# Z80Board.net
KiCad netlist of a schematic drawn in EAGLE
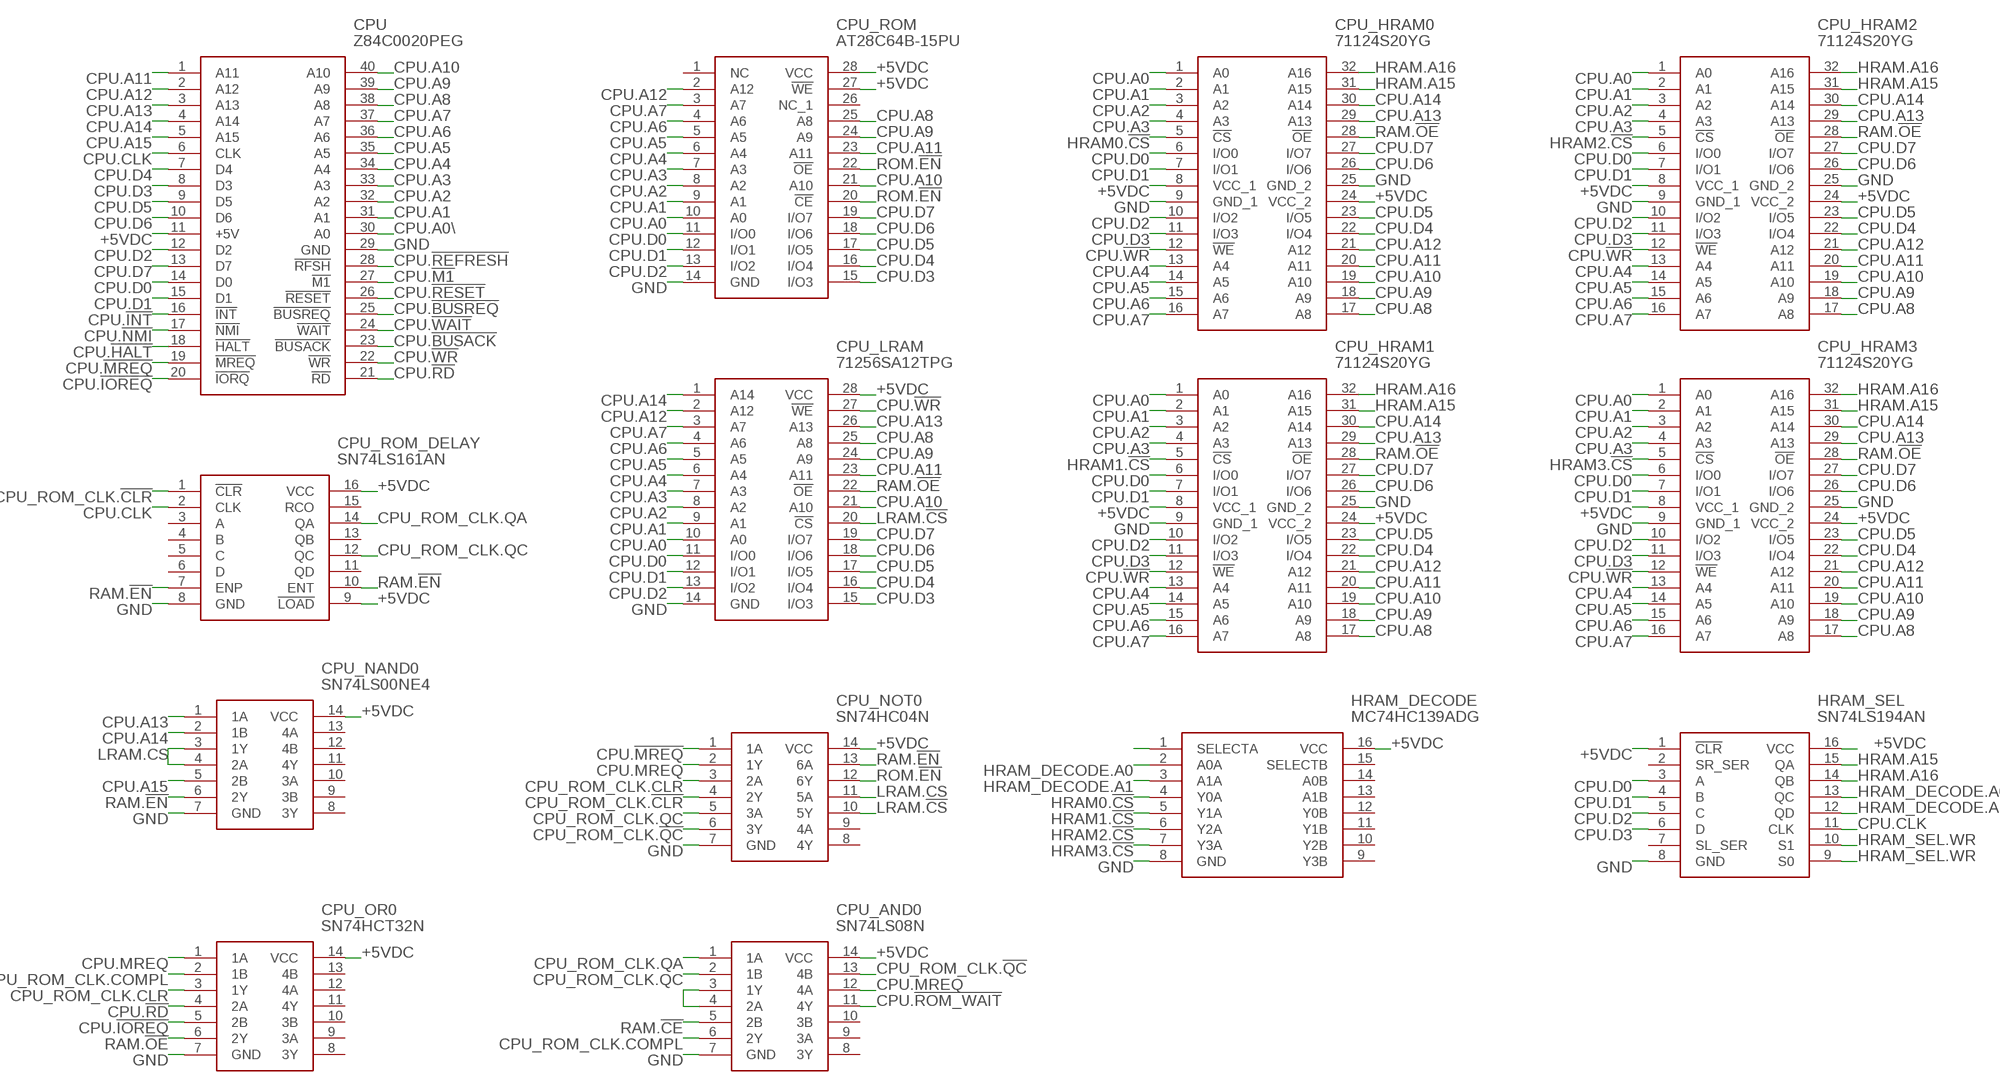
[diagram p0: schematic, sheet 1]

(export (version "E")
  (design (tool "Eeschema 10.0.6"))
  (components
    (comp (ref "CPU")
      (value "Z84C0020PEG")
      (footprint "eagle-import:DIP1612W53P254L5232H406Q40N")
      (libsource (lib "eagle-import") (part "Z84C0020PEG"))
    )
    (comp (ref "CPU_AND0")
      (value "SN74LS08N")
      (footprint "eagle-import:DIP794W53P254L1930H508Q14N")
      (fields (field (name "MOUSER_PART_NUMBER") "595-SN74LS08N") (field (name "RS_PART_NUMBER") "0307519P"))
      (libsource (lib "eagle-import") (part "SN74LS08N"))
    )
    (comp (ref "CPU_HRAM0")
      (value "71124S20YG")
      (footprint "eagle-import:71124S20YG")
      (fields (field (name "MOUSER_PART_NUMBER") "972-71124S20YG"))
      (libsource (lib "eagle-import") (part "71124S20YG"))
    )
    (comp (ref "CPU_HRAM1")
      (value "71124S20YG")
      (footprint "eagle-import:71124S20YG")
      (fields (field (name "MOUSER_PART_NUMBER") "972-71124S20YG"))
      (libsource (lib "eagle-import") (part "71124S20YG"))
    )
    (comp (ref "CPU_HRAM2")
      (value "71124S20YG")
      (footprint "eagle-import:71124S20YG")
      (fields (field (name "MOUSER_PART_NUMBER") "972-71124S20YG"))
      (libsource (lib "eagle-import") (part "71124S20YG"))
    )
    (comp (ref "CPU_HRAM3")
      (value "71124S20YG")
      (footprint "eagle-import:71124S20YG")
      (fields (field (name "MOUSER_PART_NUMBER") "972-71124S20YG"))
      (libsource (lib "eagle-import") (part "71124S20YG"))
    )
    (comp (ref "CPU_LRAM")
      (value "71256SA12TPG")
      (footprint "eagle-import:DIP851W46P254L3556H330Q28N")
      (libsource (lib "eagle-import") (part "71256SA12TPG"))
    )
    (comp (ref "CPU_NAND0")
      (value "SN74LS00NE4")
      (footprint "eagle-import:DIP794W53P254L1930H508Q14N")
      (fields (field (name "MOUSER_PART_NUMBER") "595-SN74LS00NE4"))
      (libsource (lib "eagle-import") (part "SN74LS00NE4"))
    )
    (comp (ref "CPU_NOT0")
      (value "SN74HC04N")
      (footprint "eagle-import:DIP794W53P254L1930H508Q14N")
      (fields (field (name "MOUSER_PART_NUMBER") "595-SN74HC04N") (field (name "RS_PART_NUMBER") "2175550P"))
      (libsource (lib "eagle-import") (part "SN74HC04N"))
    )
    (comp (ref "CPU_OR0")
      (value "SN74HCT32N")
      (footprint "eagle-import:DIP794W53P254L1930H508Q14N")
      (fields (field (name "MOUSER_PART_NUMBER") "595-SN74HCT32N") (field (name "RS_PART_NUMBER") "2175768P"))
      (libsource (lib "eagle-import") (part "SN74HCT32N"))
    )
    (comp (ref "CPU_ROM")
      (value "AT28C64B-15PU")
      (footprint "eagle-import:DIP1556W56P254L3702H483Q28N")
      (fields
        (field (name "MOUSER_PART_NUMBER") "556-AT28C64B15PU")
        (field (name "RS_PART_NUMBER") "2509609978")
      )
      (libsource (lib "eagle-import") (part "AT28C64B-15PU"))
    )
    (comp (ref "CPU_ROM_DELAY")
      (value "SN74LS161AN")
      (footprint "eagle-import:DIP794W53P254L1930H508Q16N")
      (fields (field (name "MOUSER_PART_NUMBER") "595-SN74LS161AN"))
      (libsource (lib "eagle-import") (part "SN74LS161AN"))
    )
    (comp (ref "HRAM_DECODE")
      (value "MC74HC139ADG")
      (footprint "eagle-import:SOIC127P600X175-16N")
      (fields
        (field (name "MOUSER_PART_NUMBER") "863-MC74HC139ADG")
        (field (name "RS_PART_NUMBER") "8061416P")
      )
      (libsource (lib "eagle-import") (part "MC74HC139ADG"))
    )
    (comp (ref "HRAM_SEL")
      (value "SN74LS194AN")
      (footprint "eagle-import:DIP794W53P254L1930H508Q16N")
      (libsource (lib "eagle-import") (part "SN74LS194AN"))
    )
  )
  (nets
    (net (code "1") (name "/+5VDC") (class "Default")
      (node (ref "CPU") (pin "11") (pinfunction "+5V_11") (pintype "power_in"))
      (node (ref "CPU_AND0") (pin "14") (pinfunction "VCC_14") (pintype "bidirectional"))
      (node (ref "CPU_HRAM0") (pin "24") (pinfunction "VCC_2_24") (pintype "bidirectional"))
      (node (ref "CPU_HRAM0") (pin "8") (pinfunction "VCC_1_8") (pintype "bidirectional"))
      (node (ref "CPU_HRAM1") (pin "24") (pinfunction "VCC_2_24") (pintype "bidirectional"))
      (node (ref "CPU_HRAM1") (pin "8") (pinfunction "VCC_1_8") (pintype "bidirectional"))
      (node (ref "CPU_HRAM2") (pin "24") (pinfunction "VCC_2_24") (pintype "bidirectional"))
      (node (ref "CPU_HRAM2") (pin "8") (pinfunction "VCC_1_8") (pintype "bidirectional"))
      (node (ref "CPU_HRAM3") (pin "24") (pinfunction "VCC_2_24") (pintype "bidirectional"))
      (node (ref "CPU_HRAM3") (pin "8") (pinfunction "VCC_1_8") (pintype "bidirectional"))
      (node (ref "CPU_LRAM") (pin "28") (pinfunction "VCC_28") (pintype "power_in"))
      (node (ref "CPU_NAND0") (pin "14") (pinfunction "VCC_14") (pintype "bidirectional"))
      (node (ref "CPU_NOT0") (pin "14") (pinfunction "VCC_14") (pintype "bidirectional"))
      (node (ref "CPU_OR0") (pin "14") (pinfunction "VCC_14") (pintype "bidirectional"))
      (node (ref "CPU_ROM") (pin "27") (pinfunction "~{WE}_27") (pintype "input"))
      (node (ref "CPU_ROM") (pin "28") (pinfunction "VCC_28") (pintype "power_in"))
      (node (ref "CPU_ROM_DELAY") (pin "16") (pinfunction "VCC_16") (pintype "bidirectional"))
      (node (ref "CPU_ROM_DELAY") (pin "9") (pinfunction "~{LOAD}_9") (pintype "bidirectional"))
      (node (ref "HRAM_DECODE") (pin "16") (pinfunction "VCC_16") (pintype "bidirectional"))
      (node (ref "HRAM_SEL") (pin "1") (pinfunction "~{CLR}_1") (pintype "input"))
      (node (ref "HRAM_SEL") (pin "16") (pinfunction "VCC_16") (pintype "power_in"))
    )
    (net (code "2") (name "/CPU.A0") (class "Default")
      (node (ref "CPU_HRAM0") (pin "1") (pinfunction "A0_1") (pintype "bidirectional"))
      (node (ref "CPU_HRAM1") (pin "1") (pinfunction "A0_1") (pintype "bidirectional"))
      (node (ref "CPU_HRAM2") (pin "1") (pinfunction "A0_1") (pintype "bidirectional"))
      (node (ref "CPU_HRAM3") (pin "1") (pinfunction "A0_1") (pintype "bidirectional"))
      (node (ref "CPU_LRAM") (pin "10") (pinfunction "A0_10") (pintype "input"))
      (node (ref "CPU_ROM") (pin "10") (pinfunction "A0_10") (pintype "input"))
    )
    (net (code "3") (name "/CPU.A0\\") (class "Default")
      (node (ref "CPU") (pin "30") (pinfunction "A0_30") (pintype "output"))
    )
    (net (code "4") (name "/CPU.A1") (class "Default")
      (node (ref "CPU") (pin "31") (pinfunction "A1_31") (pintype "output"))
      (node (ref "CPU_HRAM0") (pin "2") (pinfunction "A1_2") (pintype "bidirectional"))
      (node (ref "CPU_HRAM1") (pin "2") (pinfunction "A1_2") (pintype "bidirectional"))
      (node (ref "CPU_HRAM2") (pin "2") (pinfunction "A1_2") (pintype "bidirectional"))
      (node (ref "CPU_HRAM3") (pin "2") (pinfunction "A1_2") (pintype "bidirectional"))
      (node (ref "CPU_LRAM") (pin "9") (pinfunction "A1_9") (pintype "input"))
      (node (ref "CPU_ROM") (pin "9") (pinfunction "A1_9") (pintype "input"))
    )
    (net (code "5") (name "/CPU.A2") (class "Default")
      (node (ref "CPU") (pin "32") (pinfunction "A2_32") (pintype "output"))
      (node (ref "CPU_HRAM0") (pin "3") (pinfunction "A2_3") (pintype "bidirectional"))
      (node (ref "CPU_HRAM1") (pin "3") (pinfunction "A2_3") (pintype "bidirectional"))
      (node (ref "CPU_HRAM2") (pin "3") (pinfunction "A2_3") (pintype "bidirectional"))
      (node (ref "CPU_HRAM3") (pin "3") (pinfunction "A2_3") (pintype "bidirectional"))
      (node (ref "CPU_LRAM") (pin "8") (pinfunction "A2_8") (pintype "input"))
      (node (ref "CPU_ROM") (pin "8") (pinfunction "A2_8") (pintype "input"))
    )
    (net (code "6") (name "/CPU.A3") (class "Default")
      (node (ref "CPU") (pin "33") (pinfunction "A3_33") (pintype "output"))
      (node (ref "CPU_HRAM0") (pin "4") (pinfunction "A3_4") (pintype "bidirectional"))
      (node (ref "CPU_HRAM1") (pin "4") (pinfunction "A3_4") (pintype "bidirectional"))
      (node (ref "CPU_HRAM2") (pin "4") (pinfunction "A3_4") (pintype "bidirectional"))
      (node (ref "CPU_HRAM3") (pin "4") (pinfunction "A3_4") (pintype "bidirectional"))
      (node (ref "CPU_LRAM") (pin "7") (pinfunction "A3_7") (pintype "input"))
      (node (ref "CPU_ROM") (pin "7") (pinfunction "A3_7") (pintype "input"))
    )
    (net (code "7") (name "/CPU.A4") (class "Default")
      (node (ref "CPU") (pin "34") (pinfunction "A4_34") (pintype "output"))
      (node (ref "CPU_HRAM0") (pin "13") (pinfunction "A4_13") (pintype "bidirectional"))
      (node (ref "CPU_HRAM1") (pin "13") (pinfunction "A4_13") (pintype "bidirectional"))
      (node (ref "CPU_HRAM2") (pin "13") (pinfunction "A4_13") (pintype "bidirectional"))
      (node (ref "CPU_HRAM3") (pin "13") (pinfunction "A4_13") (pintype "bidirectional"))
      (node (ref "CPU_LRAM") (pin "6") (pinfunction "A4_6") (pintype "input"))
      (node (ref "CPU_ROM") (pin "6") (pinfunction "A4_6") (pintype "input"))
    )
    (net (code "8") (name "/CPU.A5") (class "Default")
      (node (ref "CPU") (pin "35") (pinfunction "A5_35") (pintype "output"))
      (node (ref "CPU_HRAM0") (pin "14") (pinfunction "A5_14") (pintype "bidirectional"))
      (node (ref "CPU_HRAM1") (pin "14") (pinfunction "A5_14") (pintype "bidirectional"))
      (node (ref "CPU_HRAM2") (pin "14") (pinfunction "A5_14") (pintype "bidirectional"))
      (node (ref "CPU_HRAM3") (pin "14") (pinfunction "A5_14") (pintype "bidirectional"))
      (node (ref "CPU_LRAM") (pin "5") (pinfunction "A5_5") (pintype "input"))
      (node (ref "CPU_ROM") (pin "5") (pinfunction "A5_5") (pintype "input"))
    )
    (net (code "9") (name "/CPU.A6") (class "Default")
      (node (ref "CPU") (pin "36") (pinfunction "A6_36") (pintype "output"))
      (node (ref "CPU_HRAM0") (pin "15") (pinfunction "A6_15") (pintype "bidirectional"))
      (node (ref "CPU_HRAM1") (pin "15") (pinfunction "A6_15") (pintype "bidirectional"))
      (node (ref "CPU_HRAM2") (pin "15") (pinfunction "A6_15") (pintype "bidirectional"))
      (node (ref "CPU_HRAM3") (pin "15") (pinfunction "A6_15") (pintype "bidirectional"))
      (node (ref "CPU_LRAM") (pin "4") (pinfunction "A6_4") (pintype "input"))
      (node (ref "CPU_ROM") (pin "4") (pinfunction "A6_4") (pintype "input"))
    )
    (net (code "10") (name "/CPU.A7") (class "Default")
      (node (ref "CPU") (pin "37") (pinfunction "A7_37") (pintype "output"))
      (node (ref "CPU_HRAM0") (pin "16") (pinfunction "A7_16") (pintype "bidirectional"))
      (node (ref "CPU_HRAM1") (pin "16") (pinfunction "A7_16") (pintype "bidirectional"))
      (node (ref "CPU_HRAM2") (pin "16") (pinfunction "A7_16") (pintype "bidirectional"))
      (node (ref "CPU_HRAM3") (pin "16") (pinfunction "A7_16") (pintype "bidirectional"))
      (node (ref "CPU_LRAM") (pin "3") (pinfunction "A7_3") (pintype "input"))
      (node (ref "CPU_ROM") (pin "3") (pinfunction "A7_3") (pintype "input"))
    )
    (net (code "11") (name "/CPU.A8") (class "Default")
      (node (ref "CPU") (pin "38") (pinfunction "A8_38") (pintype "output"))
      (node (ref "CPU_HRAM0") (pin "17") (pinfunction "A8_17") (pintype "bidirectional"))
      (node (ref "CPU_HRAM1") (pin "17") (pinfunction "A8_17") (pintype "bidirectional"))
      (node (ref "CPU_HRAM2") (pin "17") (pinfunction "A8_17") (pintype "bidirectional"))
      (node (ref "CPU_HRAM3") (pin "17") (pinfunction "A8_17") (pintype "bidirectional"))
      (node (ref "CPU_LRAM") (pin "25") (pinfunction "A8_25") (pintype "input"))
      (node (ref "CPU_ROM") (pin "25") (pinfunction "A8_25") (pintype "input"))
    )
    (net (code "12") (name "/CPU.A9") (class "Default")
      (node (ref "CPU") (pin "39") (pinfunction "A9_39") (pintype "output"))
      (node (ref "CPU_HRAM0") (pin "18") (pinfunction "A9_18") (pintype "bidirectional"))
      (node (ref "CPU_HRAM1") (pin "18") (pinfunction "A9_18") (pintype "bidirectional"))
      (node (ref "CPU_HRAM2") (pin "18") (pinfunction "A9_18") (pintype "bidirectional"))
      (node (ref "CPU_HRAM3") (pin "18") (pinfunction "A9_18") (pintype "bidirectional"))
      (node (ref "CPU_LRAM") (pin "24") (pinfunction "A9_24") (pintype "input"))
      (node (ref "CPU_ROM") (pin "24") (pinfunction "A9_24") (pintype "input"))
    )
    (net (code "13") (name "/CPU.A10") (class "Default")
      (node (ref "CPU") (pin "40") (pinfunction "A10_40") (pintype "output"))
      (node (ref "CPU_HRAM0") (pin "19") (pinfunction "A10_19") (pintype "bidirectional"))
      (node (ref "CPU_HRAM1") (pin "19") (pinfunction "A10_19") (pintype "bidirectional"))
      (node (ref "CPU_HRAM2") (pin "19") (pinfunction "A10_19") (pintype "bidirectional"))
      (node (ref "CPU_HRAM3") (pin "19") (pinfunction "A10_19") (pintype "bidirectional"))
      (node (ref "CPU_LRAM") (pin "21") (pinfunction "A10_21") (pintype "input"))
      (node (ref "CPU_ROM") (pin "21") (pinfunction "A10_21") (pintype "input"))
    )
    (net (code "14") (name "/CPU.A11") (class "Default")
      (node (ref "CPU") (pin "1") (pinfunction "A11_1") (pintype "bidirectional"))
      (node (ref "CPU_HRAM0") (pin "20") (pinfunction "A11_20") (pintype "bidirectional"))
      (node (ref "CPU_HRAM1") (pin "20") (pinfunction "A11_20") (pintype "bidirectional"))
      (node (ref "CPU_HRAM2") (pin "20") (pinfunction "A11_20") (pintype "bidirectional"))
      (node (ref "CPU_HRAM3") (pin "20") (pinfunction "A11_20") (pintype "bidirectional"))
      (node (ref "CPU_LRAM") (pin "23") (pinfunction "A11_23") (pintype "input"))
      (node (ref "CPU_ROM") (pin "23") (pinfunction "A11_23") (pintype "input"))
    )
    (net (code "15") (name "/CPU.A12") (class "Default")
      (node (ref "CPU") (pin "2") (pinfunction "A12_2") (pintype "bidirectional"))
      (node (ref "CPU_HRAM0") (pin "21") (pinfunction "A12_21") (pintype "bidirectional"))
      (node (ref "CPU_HRAM1") (pin "21") (pinfunction "A12_21") (pintype "bidirectional"))
      (node (ref "CPU_HRAM2") (pin "21") (pinfunction "A12_21") (pintype "bidirectional"))
      (node (ref "CPU_HRAM3") (pin "21") (pinfunction "A12_21") (pintype "bidirectional"))
      (node (ref "CPU_LRAM") (pin "2") (pinfunction "A12_2") (pintype "input"))
      (node (ref "CPU_ROM") (pin "2") (pinfunction "A12_2") (pintype "input"))
    )
    (net (code "16") (name "/CPU.A13") (class "Default")
      (node (ref "CPU") (pin "3") (pinfunction "A13_3") (pintype "bidirectional"))
      (node (ref "CPU_HRAM0") (pin "29") (pinfunction "A13_29") (pintype "bidirectional"))
      (node (ref "CPU_HRAM1") (pin "29") (pinfunction "A13_29") (pintype "bidirectional"))
      (node (ref "CPU_HRAM2") (pin "29") (pinfunction "A13_29") (pintype "bidirectional"))
      (node (ref "CPU_HRAM3") (pin "29") (pinfunction "A13_29") (pintype "bidirectional"))
      (node (ref "CPU_LRAM") (pin "26") (pinfunction "A13_26") (pintype "input"))
      (node (ref "CPU_NAND0") (pin "1") (pinfunction "1A_1") (pintype "bidirectional"))
    )
    (net (code "17") (name "/CPU.A14") (class "Default")
      (node (ref "CPU") (pin "4") (pinfunction "A14_4") (pintype "bidirectional"))
      (node (ref "CPU_HRAM0") (pin "30") (pinfunction "A14_30") (pintype "bidirectional"))
      (node (ref "CPU_HRAM1") (pin "30") (pinfunction "A14_30") (pintype "bidirectional"))
      (node (ref "CPU_HRAM2") (pin "30") (pinfunction "A14_30") (pintype "bidirectional"))
      (node (ref "CPU_HRAM3") (pin "30") (pinfunction "A14_30") (pintype "bidirectional"))
      (node (ref "CPU_LRAM") (pin "1") (pinfunction "A14_1") (pintype "input"))
      (node (ref "CPU_NAND0") (pin "2") (pinfunction "1B_2") (pintype "bidirectional"))
    )
    (net (code "18") (name "/CPU.A15") (class "Default")
      (node (ref "CPU") (pin "5") (pinfunction "A15_5") (pintype "bidirectional"))
      (node (ref "CPU_NAND0") (pin "5") (pinfunction "2B_5") (pintype "bidirectional"))
    )
    (net (code "19") (name "/CPU.CLK") (class "Default")
      (node (ref "CPU") (pin "6") (pinfunction "CLK_6") (pintype "input"))
      (node (ref "CPU_ROM_DELAY") (pin "2") (pinfunction "CLK_2") (pintype "bidirectional"))
      (node (ref "HRAM_SEL") (pin "11") (pinfunction "CLK_11") (pintype "input"))
    )
    (net (code "20") (name "/CPU.D0") (class "Default")
      (node (ref "CPU") (pin "14") (pinfunction "D0_14") (pintype "bidirectional"))
      (node (ref "CPU_HRAM0") (pin "6") (pinfunction "I/O0_6") (pintype "bidirectional"))
      (node (ref "CPU_HRAM1") (pin "6") (pinfunction "I/O0_6") (pintype "bidirectional"))
      (node (ref "CPU_HRAM2") (pin "6") (pinfunction "I/O0_6") (pintype "bidirectional"))
      (node (ref "CPU_HRAM3") (pin "6") (pinfunction "I/O0_6") (pintype "bidirectional"))
      (node (ref "CPU_LRAM") (pin "11") (pinfunction "I/O0_11") (pintype "bidirectional"))
      (node (ref "CPU_ROM") (pin "11") (pinfunction "I/O0_11") (pintype "bidirectional"))
      (node (ref "HRAM_SEL") (pin "3") (pinfunction "A_3") (pintype "input"))
    )
    (net (code "21") (name "/CPU.D1") (class "Default")
      (node (ref "CPU") (pin "15") (pinfunction "D1_15") (pintype "bidirectional"))
      (node (ref "CPU_HRAM0") (pin "7") (pinfunction "I/O1_7") (pintype "bidirectional"))
      (node (ref "CPU_HRAM1") (pin "7") (pinfunction "I/O1_7") (pintype "bidirectional"))
      (node (ref "CPU_HRAM2") (pin "7") (pinfunction "I/O1_7") (pintype "bidirectional"))
      (node (ref "CPU_HRAM3") (pin "7") (pinfunction "I/O1_7") (pintype "bidirectional"))
      (node (ref "CPU_LRAM") (pin "12") (pinfunction "I/O1_12") (pintype "bidirectional"))
      (node (ref "CPU_ROM") (pin "12") (pinfunction "I/O1_12") (pintype "bidirectional"))
      (node (ref "HRAM_SEL") (pin "4") (pinfunction "B_4") (pintype "input"))
    )
    (net (code "22") (name "/CPU.D2") (class "Default")
      (node (ref "CPU") (pin "12") (pinfunction "D2_12") (pintype "bidirectional"))
      (node (ref "CPU_HRAM0") (pin "10") (pinfunction "I/O2_10") (pintype "bidirectional"))
      (node (ref "CPU_HRAM1") (pin "10") (pinfunction "I/O2_10") (pintype "bidirectional"))
      (node (ref "CPU_HRAM2") (pin "10") (pinfunction "I/O2_10") (pintype "bidirectional"))
      (node (ref "CPU_HRAM3") (pin "10") (pinfunction "I/O2_10") (pintype "bidirectional"))
      (node (ref "CPU_LRAM") (pin "13") (pinfunction "I/O2_13") (pintype "bidirectional"))
      (node (ref "CPU_ROM") (pin "13") (pinfunction "I/O2_13") (pintype "bidirectional"))
      (node (ref "HRAM_SEL") (pin "5") (pinfunction "C_5") (pintype "input"))
    )
    (net (code "23") (name "/CPU.D3") (class "Default")
      (node (ref "CPU") (pin "8") (pinfunction "D3_8") (pintype "bidirectional"))
      (node (ref "CPU_HRAM0") (pin "11") (pinfunction "I/O3_11") (pintype "bidirectional"))
      (node (ref "CPU_HRAM1") (pin "11") (pinfunction "I/O3_11") (pintype "bidirectional"))
      (node (ref "CPU_HRAM2") (pin "11") (pinfunction "I/O3_11") (pintype "bidirectional"))
      (node (ref "CPU_HRAM3") (pin "11") (pinfunction "I/O3_11") (pintype "bidirectional"))
      (node (ref "CPU_LRAM") (pin "15") (pinfunction "I/O3_15") (pintype "bidirectional"))
      (node (ref "CPU_ROM") (pin "15") (pinfunction "I/O3_15") (pintype "bidirectional"))
      (node (ref "HRAM_SEL") (pin "6") (pinfunction "D_6") (pintype "input"))
    )
    (net (code "24") (name "/CPU.D4") (class "Default")
      (node (ref "CPU") (pin "7") (pinfunction "D4_7") (pintype "bidirectional"))
      (node (ref "CPU_HRAM0") (pin "22") (pinfunction "I/O4_22") (pintype "bidirectional"))
      (node (ref "CPU_HRAM1") (pin "22") (pinfunction "I/O4_22") (pintype "bidirectional"))
      (node (ref "CPU_HRAM2") (pin "22") (pinfunction "I/O4_22") (pintype "bidirectional"))
      (node (ref "CPU_HRAM3") (pin "22") (pinfunction "I/O4_22") (pintype "bidirectional"))
      (node (ref "CPU_LRAM") (pin "16") (pinfunction "I/O4_16") (pintype "bidirectional"))
      (node (ref "CPU_ROM") (pin "16") (pinfunction "I/O4_16") (pintype "bidirectional"))
    )
    (net (code "25") (name "/CPU.D5") (class "Default")
      (node (ref "CPU") (pin "9") (pinfunction "D5_9") (pintype "bidirectional"))
      (node (ref "CPU_HRAM0") (pin "23") (pinfunction "I/O5_23") (pintype "bidirectional"))
      (node (ref "CPU_HRAM1") (pin "23") (pinfunction "I/O5_23") (pintype "bidirectional"))
      (node (ref "CPU_HRAM2") (pin "23") (pinfunction "I/O5_23") (pintype "bidirectional"))
      (node (ref "CPU_HRAM3") (pin "23") (pinfunction "I/O5_23") (pintype "bidirectional"))
      (node (ref "CPU_LRAM") (pin "17") (pinfunction "I/O5_17") (pintype "bidirectional"))
      (node (ref "CPU_ROM") (pin "17") (pinfunction "I/O5_17") (pintype "bidirectional"))
    )
    (net (code "26") (name "/CPU.D6") (class "Default")
      (node (ref "CPU") (pin "10") (pinfunction "D6_10") (pintype "bidirectional"))
      (node (ref "CPU_HRAM0") (pin "26") (pinfunction "I/O6_26") (pintype "bidirectional"))
      (node (ref "CPU_HRAM1") (pin "26") (pinfunction "I/O6_26") (pintype "bidirectional"))
      (node (ref "CPU_HRAM2") (pin "26") (pinfunction "I/O6_26") (pintype "bidirectional"))
      (node (ref "CPU_HRAM3") (pin "26") (pinfunction "I/O6_26") (pintype "bidirectional"))
      (node (ref "CPU_LRAM") (pin "18") (pinfunction "I/O6_18") (pintype "bidirectional"))
      (node (ref "CPU_ROM") (pin "18") (pinfunction "I/O6_18") (pintype "bidirectional"))
    )
    (net (code "27") (name "/CPU.D7") (class "Default")
      (node (ref "CPU") (pin "13") (pinfunction "D7_13") (pintype "bidirectional"))
      (node (ref "CPU_HRAM0") (pin "27") (pinfunction "I/O7_27") (pintype "bidirectional"))
      (node (ref "CPU_HRAM1") (pin "27") (pinfunction "I/O7_27") (pintype "bidirectional"))
      (node (ref "CPU_HRAM2") (pin "27") (pinfunction "I/O7_27") (pintype "bidirectional"))
      (node (ref "CPU_HRAM3") (pin "27") (pinfunction "I/O7_27") (pintype "bidirectional"))
      (node (ref "CPU_LRAM") (pin "19") (pinfunction "I/O7_19") (pintype "bidirectional"))
      (node (ref "CPU_ROM") (pin "19") (pinfunction "I/O7_19") (pintype "bidirectional"))
    )
    (net (code "28") (name "/CPU.MREQ") (class "Default")
      (node (ref "CPU_AND0") (pin "12") (pinfunction "4A_12") (pintype "bidirectional"))
      (node (ref "CPU_NOT0") (pin "2") (pinfunction "1Y_2") (pintype "bidirectional"))
      (node (ref "CPU_OR0") (pin "1") (pinfunction "1A_1") (pintype "bidirectional"))
    )
    (net (code "29") (name "/CPU.~{BUSACK}") (class "Default")
      (node (ref "CPU") (pin "23") (pinfunction "~{BUSACK}_23") (pintype "output"))
    )
    (net (code "30") (name "/CPU.~{BUSREQ}") (class "Default")
      (node (ref "CPU") (pin "25") (pinfunction "~{BUSREQ}_25") (pintype "input"))
    )
    (net (code "31") (name "/CPU.~{HALT}") (class "Default")
      (node (ref "CPU") (pin "18") (pinfunction "~{HALT}_18") (pintype "output"))
    )
    (net (code "32") (name "/CPU.~{INT}") (class "Default")
      (node (ref "CPU") (pin "16") (pinfunction "~{INT}_16") (pintype "input"))
    )
    (net (code "33") (name "/CPU.~{IOREQ}") (class "Default")
      (node (ref "CPU") (pin "20") (pinfunction "~{IORQ}_20") (pintype "output"))
      (node (ref "CPU_OR0") (pin "5") (pinfunction "2B_5") (pintype "bidirectional"))
    )
    (net (code "34") (name "/CPU.~{M1}") (class "Default")
      (node (ref "CPU") (pin "27") (pinfunction "~{M1}_27") (pintype "output"))
    )
    (net (code "35") (name "/CPU.~{MREQ}") (class "Default")
      (node (ref "CPU") (pin "19") (pinfunction "~{MREQ}_19") (pintype "output"))
      (node (ref "CPU_NOT0") (pin "1") (pinfunction "1A_1") (pintype "bidirectional"))
    )
    (net (code "36") (name "/CPU.~{NMI}") (class "Default")
      (node (ref "CPU") (pin "17") (pinfunction "~{NMI}_17") (pintype "input"))
    )
    (net (code "37") (name "/CPU.~{RD}") (class "Default")
      (node (ref "CPU") (pin "21") (pinfunction "~{RD}_21") (pintype "output"))
      (node (ref "CPU_OR0") (pin "4") (pinfunction "2A_4") (pintype "bidirectional"))
    )
    (net (code "38") (name "/CPU.~{REFRESH}") (class "Default")
      (node (ref "CPU") (pin "28") (pinfunction "~{RFSH}_28") (pintype "output"))
    )
    (net (code "39") (name "/CPU.~{RESET}") (class "Default")
      (node (ref "CPU") (pin "26") (pinfunction "~{RESET}_26") (pintype "input"))
    )
    (net (code "40") (name "/CPU.~{ROM_WAIT}") (class "Default")
      (node (ref "CPU_AND0") (pin "11") (pinfunction "4Y_11") (pintype "bidirectional"))
    )
    (net (code "41") (name "/CPU.~{WAIT}") (class "Default")
      (node (ref "CPU") (pin "24") (pinfunction "~{WAIT}_24") (pintype "input"))
    )
    (net (code "42") (name "/CPU.~{WR}") (class "Default")
      (node (ref "CPU") (pin "22") (pinfunction "~{WR}_22") (pintype "output"))
      (node (ref "CPU_HRAM0") (pin "12") (pinfunction "~{WE}_12") (pintype "bidirectional"))
      (node (ref "CPU_HRAM1") (pin "12") (pinfunction "~{WE}_12") (pintype "bidirectional"))
      (node (ref "CPU_HRAM2") (pin "12") (pinfunction "~{WE}_12") (pintype "bidirectional"))
      (node (ref "CPU_HRAM3") (pin "12") (pinfunction "~{WE}_12") (pintype "bidirectional"))
      (node (ref "CPU_LRAM") (pin "27") (pinfunction "~{WE}_27") (pintype "input"))
    )
    (net (code "43") (name "/CPU_ROM_CLK.CLR") (class "Default")
      (node (ref "CPU_NOT0") (pin "3") (pinfunction "2A_3") (pintype "bidirectional"))
      (node (ref "CPU_OR0") (pin "3") (pinfunction "1Y_3") (pintype "bidirectional"))
    )
    (net (code "44") (name "/CPU_ROM_CLK.COMPL") (class "Default")
      (node (ref "CPU_AND0") (pin "6") (pinfunction "2Y_6") (pintype "bidirectional"))
      (node (ref "CPU_OR0") (pin "2") (pinfunction "1B_2") (pintype "bidirectional"))
    )
    (net (code "45") (name "/CPU_ROM_CLK.QA") (class "Default")
      (node (ref "CPU_AND0") (pin "1") (pinfunction "1A_1") (pintype "bidirectional"))
      (node (ref "CPU_ROM_DELAY") (pin "14") (pinfunction "QA_14") (pintype "bidirectional"))
    )
    (net (code "46") (name "/CPU_ROM_CLK.QC") (class "Default")
      (node (ref "CPU_AND0") (pin "2") (pinfunction "1B_2") (pintype "bidirectional"))
      (node (ref "CPU_NOT0") (pin "5") (pinfunction "3A_5") (pintype "bidirectional"))
      (node (ref "CPU_ROM_DELAY") (pin "12") (pinfunction "QC_12") (pintype "bidirectional"))
    )
    (net (code "47") (name "/CPU_ROM_CLK.~{CLR}") (class "Default")
      (node (ref "CPU_NOT0") (pin "4") (pinfunction "2Y_4") (pintype "bidirectional"))
      (node (ref "CPU_ROM_DELAY") (pin "1") (pinfunction "~{CLR}_1") (pintype "bidirectional"))
    )
    (net (code "48") (name "/CPU_ROM_CLK.~{QC}") (class "Default")
      (node (ref "CPU_AND0") (pin "13") (pinfunction "4B_13") (pintype "bidirectional"))
      (node (ref "CPU_NOT0") (pin "6") (pinfunction "3Y_6") (pintype "bidirectional"))
    )
    (net (code "49") (name "/GND") (class "Default")
      (node (ref "CPU") (pin "29") (pinfunction "GND_29") (pintype "power_in"))
      (node (ref "CPU_AND0") (pin "7") (pinfunction "GND_7") (pintype "bidirectional"))
      (node (ref "CPU_HRAM0") (pin "25") (pinfunction "GND_2_25") (pintype "bidirectional"))
      (node (ref "CPU_HRAM0") (pin "9") (pinfunction "GND_1_9") (pintype "bidirectional"))
      (node (ref "CPU_HRAM1") (pin "25") (pinfunction "GND_2_25") (pintype "bidirectional"))
      (node (ref "CPU_HRAM1") (pin "9") (pinfunction "GND_1_9") (pintype "bidirectional"))
      (node (ref "CPU_HRAM2") (pin "25") (pinfunction "GND_2_25") (pintype "bidirectional"))
      (node (ref "CPU_HRAM2") (pin "9") (pinfunction "GND_1_9") (pintype "bidirectional"))
      (node (ref "CPU_HRAM3") (pin "25") (pinfunction "GND_2_25") (pintype "bidirectional"))
      (node (ref "CPU_HRAM3") (pin "9") (pinfunction "GND_1_9") (pintype "bidirectional"))
      (node (ref "CPU_LRAM") (pin "14") (pinfunction "GND_14") (pintype "power_in"))
      (node (ref "CPU_NAND0") (pin "7") (pinfunction "GND_7") (pintype "bidirectional"))
      (node (ref "CPU_NOT0") (pin "7") (pinfunction "GND_7") (pintype "bidirectional"))
      (node (ref "CPU_OR0") (pin "7") (pinfunction "GND_7") (pintype "bidirectional"))
      (node (ref "CPU_ROM") (pin "14") (pinfunction "GND_14") (pintype "power_in"))
      (node (ref "CPU_ROM_DELAY") (pin "8") (pinfunction "GND_8") (pintype "bidirectional"))
      (node (ref "HRAM_DECODE") (pin "8") (pinfunction "GND_8") (pintype "bidirectional"))
      (node (ref "HRAM_SEL") (pin "8") (pinfunction "GND_8") (pintype "power_in"))
    )
    (net (code "50") (name "/HRAM.A15") (class "Default")
      (node (ref "CPU_HRAM0") (pin "31") (pinfunction "A15_31") (pintype "bidirectional"))
      (node (ref "CPU_HRAM1") (pin "31") (pinfunction "A15_31") (pintype "bidirectional"))
      (node (ref "CPU_HRAM2") (pin "31") (pinfunction "A15_31") (pintype "bidirectional"))
      (node (ref "CPU_HRAM3") (pin "31") (pinfunction "A15_31") (pintype "bidirectional"))
      (node (ref "HRAM_SEL") (pin "15") (pinfunction "QA_15") (pintype "output"))
    )
    (net (code "51") (name "/HRAM.A16") (class "Default")
      (node (ref "CPU_HRAM0") (pin "32") (pinfunction "A16_32") (pintype "bidirectional"))
      (node (ref "CPU_HRAM1") (pin "32") (pinfunction "A16_32") (pintype "bidirectional"))
      (node (ref "CPU_HRAM2") (pin "32") (pinfunction "A16_32") (pintype "bidirectional"))
      (node (ref "CPU_HRAM3") (pin "32") (pinfunction "A16_32") (pintype "bidirectional"))
      (node (ref "HRAM_SEL") (pin "14") (pinfunction "QB_14") (pintype "output"))
    )
    (net (code "52") (name "/HRAM0.~{CS}") (class "Default")
      (node (ref "CPU_HRAM0") (pin "5") (pinfunction "~{CS}_5") (pintype "bidirectional"))
      (node (ref "HRAM_DECODE") (pin "4") (pinfunction "Y0A_4") (pintype "bidirectional"))
    )
    (net (code "53") (name "/HRAM1.~{CS}") (class "Default")
      (node (ref "CPU_HRAM1") (pin "5") (pinfunction "~{CS}_5") (pintype "bidirectional"))
      (node (ref "HRAM_DECODE") (pin "5") (pinfunction "Y1A_5") (pintype "bidirectional"))
    )
    (net (code "54") (name "/HRAM2.~{CS}") (class "Default")
      (node (ref "CPU_HRAM2") (pin "5") (pinfunction "~{CS}_5") (pintype "bidirectional"))
      (node (ref "HRAM_DECODE") (pin "6") (pinfunction "Y2A_6") (pintype "bidirectional"))
    )
    (net (code "55") (name "/HRAM3.~{CS}") (class "Default")
      (node (ref "CPU_HRAM3") (pin "5") (pinfunction "~{CS}_5") (pintype "bidirectional"))
      (node (ref "HRAM_DECODE") (pin "7") (pinfunction "Y3A_7") (pintype "bidirectional"))
    )
    (net (code "56") (name "/HRAM_DECODE.A0") (class "Default")
      (node (ref "HRAM_DECODE") (pin "2") (pinfunction "A0A_2") (pintype "bidirectional"))
      (node (ref "HRAM_SEL") (pin "13") (pinfunction "QC_13") (pintype "output"))
    )
    (net (code "57") (name "/HRAM_DECODE.A1") (class "Default")
      (node (ref "HRAM_DECODE") (pin "3") (pinfunction "A1A_3") (pintype "bidirectional"))
      (node (ref "HRAM_SEL") (pin "12") (pinfunction "QD_12") (pintype "output"))
    )
    (net (code "58") (name "/HRAM_SEL.WR") (class "Default")
      (node (ref "HRAM_SEL") (pin "10") (pinfunction "S1_10") (pintype "input"))
      (node (ref "HRAM_SEL") (pin "9") (pinfunction "S0_9") (pintype "input"))
    )
    (net (code "59") (name "/LRAM.CS") (class "Default")
      (node (ref "CPU_NAND0") (pin "3") (pinfunction "1Y_3") (pintype "bidirectional"))
      (node (ref "CPU_NAND0") (pin "4") (pinfunction "2A_4") (pintype "bidirectional"))
      (node (ref "CPU_NOT0") (pin "11") (pinfunction "5A_11") (pintype "bidirectional"))
    )
    (net (code "60") (name "/LRAM.~{CS}") (class "Default")
      (node (ref "CPU_LRAM") (pin "20") (pinfunction "~{CS}_20") (pintype "input"))
      (node (ref "CPU_NOT0") (pin "10") (pinfunction "5Y_10") (pintype "bidirectional"))
    )
    (net (code "61") (name "/RAM.~{CE}") (class "Default")
      (node (ref "CPU_AND0") (pin "5") (pinfunction "2B_5") (pintype "bidirectional"))
    )
    (net (code "62") (name "/RAM.~{EN}") (class "Default")
      (node (ref "CPU_NAND0") (pin "6") (pinfunction "2Y_6") (pintype "bidirectional"))
      (node (ref "CPU_NOT0") (pin "13") (pinfunction "6A_13") (pintype "bidirectional"))
      (node (ref "CPU_ROM_DELAY") (pin "10") (pinfunction "ENT_10") (pintype "bidirectional"))
      (node (ref "CPU_ROM_DELAY") (pin "7") (pinfunction "ENP_7") (pintype "bidirectional"))
    )
    (net (code "63") (name "/RAM.~{OE}") (class "Default")
      (node (ref "CPU_HRAM0") (pin "28") (pinfunction "~{OE}_28") (pintype "bidirectional"))
      (node (ref "CPU_HRAM1") (pin "28") (pinfunction "~{OE}_28") (pintype "bidirectional"))
      (node (ref "CPU_HRAM2") (pin "28") (pinfunction "~{OE}_28") (pintype "bidirectional"))
      (node (ref "CPU_HRAM3") (pin "28") (pinfunction "~{OE}_28") (pintype "bidirectional"))
      (node (ref "CPU_LRAM") (pin "22") (pinfunction "~{OE}_22") (pintype "input"))
      (node (ref "CPU_OR0") (pin "6") (pinfunction "2Y_6") (pintype "bidirectional"))
    )
    (net (code "64") (name "/ROM.~{EN}") (class "Default")
      (node (ref "CPU_NOT0") (pin "12") (pinfunction "6Y_12") (pintype "bidirectional"))
      (node (ref "CPU_ROM") (pin "20") (pinfunction "~{CE}_20") (pintype "input"))
      (node (ref "CPU_ROM") (pin "22") (pinfunction "~{OE}_22") (pintype "input"))
    )
    (net (code "65") (name "Net-(CPU_AND0-1Y)") (class "Default")
      (node (ref "CPU_AND0") (pin "3") (pinfunction "1Y_3") (pintype "bidirectional"))
      (node (ref "CPU_AND0") (pin "4") (pinfunction "2A_4") (pintype "bidirectional"))
    )
    (net (code "66") (name "unconnected-(CPU_AND0-3A-Pad9)") (class "Default")
      (node (ref "CPU_AND0") (pin "9") (pinfunction "3A_9") (pintype "bidirectional"))
    )
    (net (code "67") (name "unconnected-(CPU_AND0-3B-Pad10)") (class "Default")
      (node (ref "CPU_AND0") (pin "10") (pinfunction "3B_10") (pintype "bidirectional"))
    )
    (net (code "68") (name "unconnected-(CPU_AND0-3Y-Pad8)") (class "Default")
      (node (ref "CPU_AND0") (pin "8") (pinfunction "3Y_8") (pintype "bidirectional"))
    )
    (net (code "69") (name "unconnected-(CPU_NAND0-3A-Pad10)") (class "Default")
      (node (ref "CPU_NAND0") (pin "10") (pinfunction "3A_10") (pintype "bidirectional"))
    )
    (net (code "70") (name "unconnected-(CPU_NAND0-3B-Pad9)") (class "Default")
      (node (ref "CPU_NAND0") (pin "9") (pinfunction "3B_9") (pintype "bidirectional"))
    )
    (net (code "71") (name "unconnected-(CPU_NAND0-3Y-Pad8)") (class "Default")
      (node (ref "CPU_NAND0") (pin "8") (pinfunction "3Y_8") (pintype "bidirectional"))
    )
    (net (code "72") (name "unconnected-(CPU_NAND0-4A-Pad13)") (class "Default")
      (node (ref "CPU_NAND0") (pin "13") (pinfunction "4A_13") (pintype "bidirectional"))
    )
    (net (code "73") (name "unconnected-(CPU_NAND0-4B-Pad12)") (class "Default")
      (node (ref "CPU_NAND0") (pin "12") (pinfunction "4B_12") (pintype "bidirectional"))
    )
    (net (code "74") (name "unconnected-(CPU_NAND0-4Y-Pad11)") (class "Default")
      (node (ref "CPU_NAND0") (pin "11") (pinfunction "4Y_11") (pintype "bidirectional"))
    )
    (net (code "75") (name "unconnected-(CPU_NOT0-4A-Pad9)") (class "Default")
      (node (ref "CPU_NOT0") (pin "9") (pinfunction "4A_9") (pintype "bidirectional"))
    )
    (net (code "76") (name "unconnected-(CPU_NOT0-4Y-Pad8)") (class "Default")
      (node (ref "CPU_NOT0") (pin "8") (pinfunction "4Y_8") (pintype "bidirectional"))
    )
    (net (code "77") (name "unconnected-(CPU_OR0-3A-Pad9)") (class "Default")
      (node (ref "CPU_OR0") (pin "9") (pinfunction "3A_9") (pintype "bidirectional"))
    )
    (net (code "78") (name "unconnected-(CPU_OR0-3B-Pad10)") (class "Default")
      (node (ref "CPU_OR0") (pin "10") (pinfunction "3B_10") (pintype "bidirectional"))
    )
    (net (code "79") (name "unconnected-(CPU_OR0-3Y-Pad8)") (class "Default")
      (node (ref "CPU_OR0") (pin "8") (pinfunction "3Y_8") (pintype "bidirectional"))
    )
    (net (code "80") (name "unconnected-(CPU_OR0-4A-Pad12)") (class "Default")
      (node (ref "CPU_OR0") (pin "12") (pinfunction "4A_12") (pintype "bidirectional"))
    )
    (net (code "81") (name "unconnected-(CPU_OR0-4B-Pad13)") (class "Default")
      (node (ref "CPU_OR0") (pin "13") (pinfunction "4B_13") (pintype "bidirectional"))
    )
    (net (code "82") (name "unconnected-(CPU_OR0-4Y-Pad11)") (class "Default")
      (node (ref "CPU_OR0") (pin "11") (pinfunction "4Y_11") (pintype "bidirectional"))
    )
    (net (code "83") (name "unconnected-(CPU_ROM-NC-Pad1)") (class "Default")
      (node (ref "CPU_ROM") (pin "1") (pinfunction "NC_1") (pintype "no_connect"))
    )
    (net (code "84") (name "unconnected-(CPU_ROM-NC_1-Pad26)") (class "Default")
      (node (ref "CPU_ROM") (pin "26") (pinfunction "NC_1_26") (pintype "bidirectional"))
    )
    (net (code "85") (name "unconnected-(CPU_ROM_DELAY-A-Pad3)") (class "Default")
      (node (ref "CPU_ROM_DELAY") (pin "3") (pinfunction "A_3") (pintype "bidirectional"))
    )
    (net (code "86") (name "unconnected-(CPU_ROM_DELAY-B-Pad4)") (class "Default")
      (node (ref "CPU_ROM_DELAY") (pin "4") (pinfunction "B_4") (pintype "bidirectional"))
    )
    (net (code "87") (name "unconnected-(CPU_ROM_DELAY-C-Pad5)") (class "Default")
      (node (ref "CPU_ROM_DELAY") (pin "5") (pinfunction "C_5") (pintype "bidirectional"))
    )
    (net (code "88") (name "unconnected-(CPU_ROM_DELAY-D-Pad6)") (class "Default")
      (node (ref "CPU_ROM_DELAY") (pin "6") (pinfunction "D_6") (pintype "bidirectional"))
    )
    (net (code "89") (name "unconnected-(CPU_ROM_DELAY-QB-Pad13)") (class "Default")
      (node (ref "CPU_ROM_DELAY") (pin "13") (pinfunction "QB_13") (pintype "bidirectional"))
    )
    (net (code "90") (name "unconnected-(CPU_ROM_DELAY-QD-Pad11)") (class "Default")
      (node (ref "CPU_ROM_DELAY") (pin "11") (pinfunction "QD_11") (pintype "bidirectional"))
    )
    (net (code "91") (name "unconnected-(CPU_ROM_DELAY-RCO-Pad15)") (class "Default")
      (node (ref "CPU_ROM_DELAY") (pin "15") (pinfunction "RCO_15") (pintype "bidirectional"))
    )
    (net (code "92") (name "unconnected-(HRAM_DECODE-A0B-Pad14)") (class "Default")
      (node (ref "HRAM_DECODE") (pin "14") (pinfunction "A0B_14") (pintype "bidirectional"))
    )
    (net (code "93") (name "unconnected-(HRAM_DECODE-A1B-Pad13)") (class "Default")
      (node (ref "HRAM_DECODE") (pin "13") (pinfunction "A1B_13") (pintype "bidirectional"))
    )
    (net (code "94") (name "unconnected-(HRAM_DECODE-SELECTA-Pad1)") (class "Default")
      (node (ref "HRAM_DECODE") (pin "1") (pinfunction "SELECTA_1") (pintype "bidirectional"))
    )
    (net (code "95") (name "unconnected-(HRAM_DECODE-SELECTB-Pad15)") (class "Default")
      (node (ref "HRAM_DECODE") (pin "15") (pinfunction "SELECTB_15") (pintype "bidirectional"))
    )
    (net (code "96") (name "unconnected-(HRAM_DECODE-Y0B-Pad12)") (class "Default")
      (node (ref "HRAM_DECODE") (pin "12") (pinfunction "Y0B_12") (pintype "bidirectional"))
    )
    (net (code "97") (name "unconnected-(HRAM_DECODE-Y1B-Pad11)") (class "Default")
      (node (ref "HRAM_DECODE") (pin "11") (pinfunction "Y1B_11") (pintype "bidirectional"))
    )
    (net (code "98") (name "unconnected-(HRAM_DECODE-Y2B-Pad10)") (class "Default")
      (node (ref "HRAM_DECODE") (pin "10") (pinfunction "Y2B_10") (pintype "bidirectional"))
    )
    (net (code "99") (name "unconnected-(HRAM_DECODE-Y3B-Pad9)") (class "Default")
      (node (ref "HRAM_DECODE") (pin "9") (pinfunction "Y3B_9") (pintype "bidirectional"))
    )
    (net (code "100") (name "unconnected-(HRAM_SEL-SL_SER-Pad7)") (class "Default")
      (node (ref "HRAM_SEL") (pin "7") (pinfunction "SL_SER_7") (pintype "bidirectional"))
    )
    (net (code "101") (name "unconnected-(HRAM_SEL-SR_SER-Pad2)") (class "Default")
      (node (ref "HRAM_SEL") (pin "2") (pinfunction "SR_SER_2") (pintype "bidirectional"))
    )
  )
)
